# 3_ports.net
KiCad netlist of a schematic drawn in Altium Designer
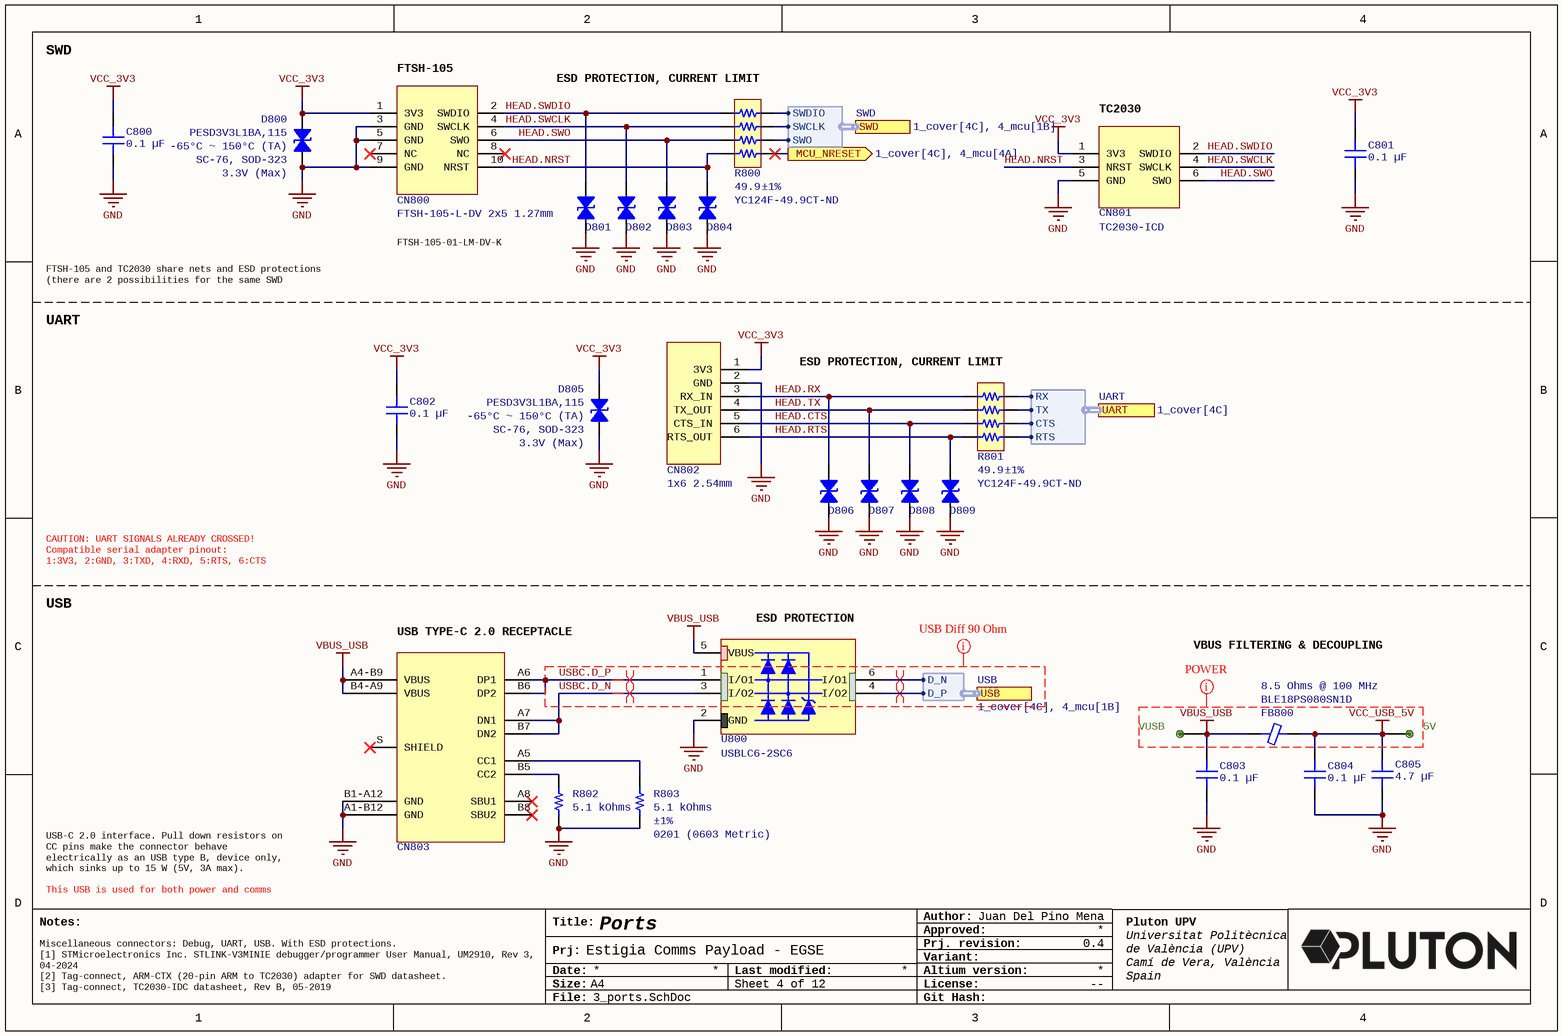
[diagram p0: 3_ports.SchDoc]

(export (version "E")
  (design (tool "Eeschema 10.0.6"))
  (components
    (comp (ref "5V")
      (value "~")
      (footprint "testpoints:testpoint_via")
      (description "Test point, thru-hole")
      (libsource (lib "testpoints") (part "TestPoint-VIA"))
    )
    (comp (ref "C800")
      (value "0.1 µF")
      (footprint "CAP 0402_1005")
      (description "CAP CER 0402 0.1UF 16V X7R 10%")
      (fields (field (name "PART NUMBER") "C0402C104K4RECAUTO") (field (name "MANUFACTURER") "KEMET"))
      (libsource (lib "Celestial Altium Library - altium_library") (part "Capacitor"))
    )
    (comp (ref "C801")
      (value "0.1 µF")
      (footprint "CAP 0402_1005")
      (description "CAP CER 0402 0.1UF 16V X7R 10%")
      (fields (field (name "PART NUMBER") "C0402C104K4RECAUTO") (field (name "MANUFACTURER") "KEMET"))
      (libsource (lib "Celestial Altium Library - altium_library") (part "Capacitor"))
    )
    (comp (ref "C802")
      (value "0.1 µF")
      (footprint "CAP 0402_1005")
      (description "CAP CER 0402 0.1UF 16V X7R 10%")
      (fields (field (name "PART NUMBER") "C0402C104K4RECAUTO") (field (name "MANUFACTURER") "KEMET"))
      (libsource (lib "Celestial Altium Library - altium_library") (part "Capacitor"))
    )
    (comp (ref "C803")
      (value "0.1 µF")
      (footprint "CAP 0402_1005")
      (description "CAP CER 0402 0.1UF 16V X7R 10%")
      (fields (field (name "PART NUMBER") "C0402C104K4RECAUTO") (field (name "MANUFACTURER") "KEMET"))
      (libsource (lib "Celestial Altium Library - altium_library") (part "Capacitor"))
    )
    (comp (ref "C804")
      (value "0.1 µF")
      (footprint "CAP 0402_1005")
      (description "CAP CER 0402 0.1UF 16V X7R 10%")
      (fields (field (name "PART NUMBER") "C0402C104K4RECAUTO") (field (name "MANUFACTURER") "KEMET"))
      (libsource (lib "Celestial Altium Library - altium_library") (part "Capacitor"))
    )
    (comp (ref "C805")
      (value "4.7 µF")
      (footprint "CAP 0603_1608")
      (description "CAP CER 4.7UF 16V X7R 0603")
      (fields
        (field (name "PART NUMBER") "GRM188Z71C475KE21J")
        (field (name "MANUFACTURER") "Murata Electronics")
      )
      (libsource (lib "Celestial Altium Library - altium_library") (part "Capacitor"))
    )
    (comp (ref "CN800")
      (value "FTSH-105-L-DV 2x5 1.27mm")
      (footprint "connectors:Samtec ftsh-105-l-dv")
      (description "Samtec FTSH-105-L-DV")
      (libsource (lib "connectors") (part "SWD Header 2x5 1.27mm"))
    )
    (comp (ref "CN801")
      (value "TC2030-ICD")
      (footprint "TC2030-MCP-NL")
      (libsource (lib "TC2030") (part "TC2030-ICD"))
    )
    (comp (ref "CN802")
      (value "1x6 2.54mm")
      (footprint "CONNECTORS:Header 1x6 2.54mm")
      (description "Header 1x6 2.54mm")
      (libsource (lib "connectors") (part "UART Header 1x6 2.54mm"))
    )
    (comp (ref "CN803")
      (value "USB4105-GF-A")
      (footprint "connectors:USB4105-GF-A")
      (description "z")
      (libsource (lib "usb") (part "USB-C USB4105-GF-A"))
    )
    (comp (ref "D800")
      (value "PESD3V3L1BA,115")
      (footprint "SOD323")
      (description "TVS DIODE 3.3VWM 26VC SOD323")
      (fields
        (field (name "PART NUMBER") "PESD3V3L1BA,115")
        (field (name "MANUFACTURER") "Nexperia USA Inc.")
        (field (name "OPERATING TEMPERATURE") "-65°C ~ 150°C (TA)")
        (field (name "PACKAGE / CASE") "SC-76, SOD-323")
        (field (name "VOLTAGE - REVERSE STANDOFF (TYP)") "3.3V (Max)")
      )
      (libsource (lib "Celestial Altium Library - altium_library") (part "Diode TVS"))
    )
    (comp (ref "D801")
      (value "PESD3V3L1BA,115")
      (footprint "SOD323")
      (description "TVS DIODE 3.3VWM 26VC SOD323")
      (fields (field (name "MANUFACTURER") "Nexperia USA Inc."))
      (libsource (lib "Celestial Altium Library - altium_library") (part "Diode TVS"))
    )
    (comp (ref "D802")
      (value "PESD3V3L1BA,115")
      (footprint "SOD323")
      (description "TVS DIODE 3.3VWM 26VC SOD323")
      (fields (field (name "MANUFACTURER") "Nexperia USA Inc."))
      (libsource (lib "Celestial Altium Library - altium_library") (part "Diode TVS"))
    )
    (comp (ref "D803")
      (value "PESD3V3L1BA,115")
      (footprint "SOD323")
      (description "TVS DIODE 3.3VWM 26VC SOD323")
      (fields (field (name "MANUFACTURER") "Nexperia USA Inc."))
      (libsource (lib "Celestial Altium Library - altium_library") (part "Diode TVS"))
    )
    (comp (ref "D804")
      (value "PESD3V3L1BA,115")
      (footprint "SOD323")
      (description "TVS DIODE 3.3VWM 26VC SOD323")
      (fields (field (name "MANUFACTURER") "Nexperia USA Inc."))
      (libsource (lib "Celestial Altium Library - altium_library") (part "Diode TVS"))
    )
    (comp (ref "D805")
      (value "PESD3V3L1BA,115")
      (footprint "SOD323")
      (description "TVS DIODE 3.3VWM 26VC SOD323")
      (fields
        (field (name "PART NUMBER") "PESD3V3L1BA,115")
        (field (name "MANUFACTURER") "Nexperia USA Inc.")
        (field (name "OPERATING TEMPERATURE") "-65°C ~ 150°C (TA)")
        (field (name "PACKAGE / CASE") "SC-76, SOD-323")
        (field (name "VOLTAGE - REVERSE STANDOFF (TYP)") "3.3V (Max)")
      )
      (libsource (lib "Celestial Altium Library - altium_library") (part "Diode TVS"))
    )
    (comp (ref "D806")
      (value "PESD3V3L1BA,115")
      (footprint "SOD323")
      (description "TVS DIODE 3.3VWM 26VC SOD323")
      (fields (field (name "MANUFACTURER") "Nexperia USA Inc."))
      (libsource (lib "Celestial Altium Library - altium_library") (part "Diode TVS"))
    )
    (comp (ref "D807")
      (value "PESD3V3L1BA,115")
      (footprint "SOD323")
      (description "TVS DIODE 3.3VWM 26VC SOD323")
      (fields (field (name "MANUFACTURER") "Nexperia USA Inc."))
      (libsource (lib "Celestial Altium Library - altium_library") (part "Diode TVS"))
    )
    (comp (ref "D808")
      (value "PESD3V3L1BA,115")
      (footprint "SOD323")
      (description "TVS DIODE 3.3VWM 26VC SOD323")
      (fields (field (name "MANUFACTURER") "Nexperia USA Inc."))
      (libsource (lib "Celestial Altium Library - altium_library") (part "Diode TVS"))
    )
    (comp (ref "D809")
      (value "PESD3V3L1BA,115")
      (footprint "SOD323")
      (description "TVS DIODE 3.3VWM 26VC SOD323")
      (fields (field (name "MANUFACTURER") "Nexperia USA Inc."))
      (libsource (lib "Celestial Altium Library - altium_library") (part "Diode TVS"))
    )
    (comp (ref "FB800")
      (value "8.5 Ohms @ 100 MHz")
      (footprint "FER 0603_1608")
      (description "FERRITE BEAD 8.5 OHM 0603 1LN")
      (fields
        (field (name "PART NUMBER") "BLE18PS080SN1D")
        (field (name "IMPEDANCE @ FREQUENCY") "8.5 Ohms @ 100 MHz")
        (field (name "MANUFACTURER") "Murata Electronics")
      )
      (libsource (lib "Celestial Altium Library - altium_library") (part "Ferrite Chip"))
    )
    (comp (ref "R800")
      (value "YC124-FR-0749R9L")
      (footprint "RESNET 0804-8 CONVEX")
      (description "RES ARRAY 4 RES 49.9 OHM 0804")
      (fields
        (field (name "MANUFACTURER") "Yageo")
        (field (name "RESISTANCE (OHMS)") "49.9")
        (field (name "SUPPLIER PART NUMBER 1") "YC124F-49.9CT-ND")
        (field (name "TOLERANCE") "±1%")
      )
      (libsource (lib "Celestial Altium Library - altium_library") (part "Resistor Array (4 circuit)"))
    )
    (comp (ref "R801")
      (value "YC124-FR-0749R9L")
      (footprint "RESNET 0804-8 CONVEX")
      (description "RES ARRAY 4 RES 49.9 OHM 0804")
      (fields
        (field (name "MANUFACTURER") "Yageo")
        (field (name "RESISTANCE (OHMS)") "49.9")
        (field (name "SUPPLIER PART NUMBER 1") "YC124F-49.9CT-ND")
        (field (name "TOLERANCE") "±1%")
      )
      (libsource (lib "Celestial Altium Library - altium_library") (part "Resistor Array (4 circuit)"))
    )
    (comp (ref "R802")
      (value "5.1 kOhms")
      (footprint "RES 0201_0603")
      (description "RES SMD 5.1K OHM 1% 1/20W 0201")
      (fields (field (name "PART NUMBER") "AC0201FR-075K1L") (field (name "MANUFACTURER") "Yageo"))
      (libsource (lib "Celestial Altium Library - altium_library") (part "Resistor"))
    )
    (comp (ref "R803")
      (value "5.1 kOhms")
      (footprint "RES 0201_0603")
      (description "RES SMD 5.1K OHM 1% 1/20W 0201")
      (fields
        (field (name "PART NUMBER") "AC0201FR-075K1L")
        (field (name "DEVICE PACKAGE") "0201 (0603 Metric)")
        (field (name "MANUFACTURER") "Yageo")
        (field (name "TOLERANCE") "±1%")
      )
      (libsource (lib "Celestial Altium Library - altium_library") (part "Resistor"))
    )
    (comp (ref "U800")
      (value "USBLC6-2SC6")
      (footprint "ics:SOT23-6L")
      (libsource (lib "usb") (part "USBLC6-2SC6"))
    )
    (comp (ref "VUSB")
      (value "~")
      (footprint "testpoints:testpoint_via")
      (description "Test point, thru-hole")
      (libsource (lib "testpoints") (part "TestPoint-VIA"))
    )
  )
  (nets
    (net (code "4") (name "/CTS") (class "Default")
      (node (ref "R801") (pin "6") (pinfunction "6_6") (pintype "passive"))
    )
    (net (code "5") (name "/D_N") (class "Default")
      (node (ref "U800") (pin "6") (pinfunction "I/O1_6") (pintype "passive"))
    )
    (net (code "6") (name "/D_P") (class "Default")
      (node (ref "U800") (pin "4") (pinfunction "I/O2_4") (pintype "passive"))
    )
    (net (code "7") (name "/HEAD.CTS") (class "Default")
      (node (ref "CN802") (pin "5") (pinfunction "CTS_IN_5") (pintype "passive"))
      (node (ref "D808") (pin "2") (pinfunction "2_2") (pintype "passive"))
      (node (ref "R801") (pin "3") (pinfunction "3_3") (pintype "passive"))
    )
    (net (code "8") (name "/HEAD.NRST") (class "Default")
      (node (ref "CN800") (pin "10") (pinfunction "NRST_10") (pintype "passive"))
      (node (ref "CN801") (pin "3") (pinfunction "NRST_3") (pintype "passive"))
      (node (ref "D804") (pin "2") (pinfunction "2_2") (pintype "passive"))
      (node (ref "R800") (pin "4") (pinfunction "4_4") (pintype "passive"))
    )
    (net (code "9") (name "/HEAD.RTS") (class "Default")
      (node (ref "CN802") (pin "6") (pinfunction "RTS_OUT_6") (pintype "passive"))
      (node (ref "D809") (pin "2") (pinfunction "2_2") (pintype "passive"))
      (node (ref "R801") (pin "4") (pinfunction "4_4") (pintype "passive"))
    )
    (net (code "10") (name "/HEAD.RX") (class "Default")
      (node (ref "CN802") (pin "3") (pinfunction "RX_IN_3") (pintype "passive"))
      (node (ref "D806") (pin "2") (pinfunction "2_2") (pintype "passive"))
      (node (ref "R801") (pin "1") (pinfunction "1_1") (pintype "passive"))
    )
    (net (code "11") (name "/HEAD.SWCLK") (class "Default")
      (node (ref "CN800") (pin "4") (pinfunction "SWCLK_4") (pintype "passive"))
      (node (ref "CN801") (pin "4") (pinfunction "SWCLK_4") (pintype "passive"))
      (node (ref "D802") (pin "2") (pinfunction "2_2") (pintype "passive"))
      (node (ref "R800") (pin "2") (pinfunction "2_2") (pintype "passive"))
    )
    (net (code "12") (name "/HEAD.SWDIO") (class "Default")
      (node (ref "CN800") (pin "2") (pinfunction "SWDIO_2") (pintype "passive"))
      (node (ref "CN801") (pin "2") (pinfunction "SWDIO_2") (pintype "passive"))
      (node (ref "D801") (pin "2") (pinfunction "2_2") (pintype "passive"))
      (node (ref "R800") (pin "1") (pinfunction "1_1") (pintype "passive"))
    )
    (net (code "13") (name "/HEAD.SWO") (class "Default")
      (node (ref "CN800") (pin "6") (pinfunction "SWO_6") (pintype "passive"))
      (node (ref "CN801") (pin "6") (pinfunction "SWO_6") (pintype "passive"))
      (node (ref "D803") (pin "2") (pinfunction "2_2") (pintype "passive"))
      (node (ref "R800") (pin "3") (pinfunction "3_3") (pintype "passive"))
    )
    (net (code "14") (name "/HEAD.TX") (class "Default")
      (node (ref "CN802") (pin "4") (pinfunction "TX_OUT_4") (pintype "passive"))
      (node (ref "D807") (pin "2") (pinfunction "2_2") (pintype "passive"))
      (node (ref "R801") (pin "2") (pinfunction "2_2") (pintype "passive"))
    )
    (net (code "15") (name "/MCU_NRESET") (class "Default")
      (node (ref "R800") (pin "5") (pinfunction "5_5") (pintype "passive+no_connect"))
    )
    (net (code "16") (name "/RTS") (class "Default")
      (node (ref "R801") (pin "5") (pinfunction "5_5") (pintype "passive"))
    )
    (net (code "17") (name "/RX") (class "Default")
      (node (ref "R801") (pin "8") (pinfunction "8_8") (pintype "passive"))
    )
    (net (code "18") (name "/SWCLK") (class "Default")
      (node (ref "R800") (pin "7") (pinfunction "7_7") (pintype "passive"))
    )
    (net (code "19") (name "/SWDIO") (class "Default")
      (node (ref "R800") (pin "8") (pinfunction "8_8") (pintype "passive"))
    )
    (net (code "20") (name "/SWO") (class "Default")
      (node (ref "R800") (pin "6") (pinfunction "6_6") (pintype "passive"))
    )
    (net (code "21") (name "/TX") (class "Default")
      (node (ref "R801") (pin "7") (pinfunction "7_7") (pintype "passive"))
    )
    (net (code "22") (name "/USBC.D_N") (class "Default")
      (node (ref "CN803") (pin "A7") (pinfunction "DN1_A7") (pintype "passive"))
      (node (ref "CN803") (pin "B7") (pinfunction "DN2_B7") (pintype "passive"))
      (node (ref "U800") (pin "3") (pinfunction "I/O2_3") (pintype "passive"))
    )
    (net (code "23") (name "/USBC.D_P") (class "Default")
      (node (ref "CN803") (pin "A6") (pinfunction "DP1_A6") (pintype "passive"))
      (node (ref "CN803") (pin "B6") (pinfunction "DP2_B6") (pintype "passive"))
      (node (ref "U800") (pin "1") (pinfunction "I/O1_1") (pintype "passive"))
    )
    (net (code "27") (name "GND") (class "Default")
      (node (ref "C800") (pin "1") (pinfunction "1_1") (pintype "passive"))
      (node (ref "C801") (pin "1") (pinfunction "1_1") (pintype "passive"))
      (node (ref "C802") (pin "1") (pinfunction "1_1") (pintype "passive"))
      (node (ref "C803") (pin "1") (pinfunction "1_1") (pintype "passive"))
      (node (ref "C804") (pin "1") (pinfunction "1_1") (pintype "passive"))
      (node (ref "C805") (pin "1") (pinfunction "1_1") (pintype "passive"))
      (node (ref "CN800") (pin "3") (pinfunction "GND_3") (pintype "passive"))
      (node (ref "CN800") (pin "5") (pinfunction "GND_5") (pintype "passive"))
      (node (ref "CN800") (pin "9") (pinfunction "GND_9") (pintype "passive"))
      (node (ref "CN801") (pin "5") (pinfunction "GND_5") (pintype "passive"))
      (node (ref "CN802") (pin "2") (pinfunction "GND_2") (pintype "power_in"))
      (node (ref "CN803") (pin "A1-B12") (pinfunction "GND_A1-B12") (pintype "power_in"))
      (node (ref "CN803") (pin "B1-A12") (pinfunction "GND_B1-A12") (pintype "power_in"))
      (node (ref "D800") (pin "1") (pinfunction "1_1") (pintype "passive"))
      (node (ref "D801") (pin "1") (pinfunction "1_1") (pintype "passive"))
      (node (ref "D802") (pin "1") (pinfunction "1_1") (pintype "passive"))
      (node (ref "D803") (pin "1") (pinfunction "1_1") (pintype "passive"))
      (node (ref "D804") (pin "1") (pinfunction "1_1") (pintype "passive"))
      (node (ref "D805") (pin "1") (pinfunction "1_1") (pintype "passive"))
      (node (ref "D806") (pin "1") (pinfunction "1_1") (pintype "passive"))
      (node (ref "D807") (pin "1") (pinfunction "1_1") (pintype "passive"))
      (node (ref "D808") (pin "1") (pinfunction "1_1") (pintype "passive"))
      (node (ref "D809") (pin "1") (pinfunction "1_1") (pintype "passive"))
      (node (ref "R802") (pin "1") (pinfunction "1_1") (pintype "passive"))
      (node (ref "R803") (pin "1") (pinfunction "1_1") (pintype "passive"))
      (node (ref "U800") (pin "2") (pinfunction "GND_2") (pintype "passive"))
    )
    (net (code "28") (name "Net-(CN803-CC1)") (class "Default")
      (node (ref "CN803") (pin "A5") (pinfunction "CC1_A5") (pintype "passive"))
      (node (ref "R803") (pin "2") (pinfunction "2_2") (pintype "passive"))
    )
    (net (code "29") (name "Net-(CN803-CC2)") (class "Default")
      (node (ref "CN803") (pin "B5") (pinfunction "CC2_B5") (pintype "passive"))
      (node (ref "R802") (pin "2") (pinfunction "2_2") (pintype "passive"))
    )
    (net (code "30") (name "VBUS_USB") (class "Default")
      (node (ref "C803") (pin "2") (pinfunction "2_2") (pintype "passive"))
      (node (ref "CN803") (pin "A4-B9") (pinfunction "VBUS_A4-B9") (pintype "power_in"))
      (node (ref "CN803") (pin "B4-A9") (pinfunction "VBUS_B4-A9") (pintype "power_in"))
      (node (ref "FB800") (pin "1") (pinfunction "1_1") (pintype "passive"))
      (node (ref "U800") (pin "5") (pinfunction "VBUS_5") (pintype "passive"))
      (node (ref "VUSB") (pin "0") (pinfunction "0_0") (pintype "passive"))
    )
    (net (code "31") (name "VCC_3V3") (class "Default")
      (node (ref "C800") (pin "2") (pinfunction "2_2") (pintype "passive"))
      (node (ref "C801") (pin "2") (pinfunction "2_2") (pintype "passive"))
      (node (ref "C802") (pin "2") (pinfunction "2_2") (pintype "passive"))
      (node (ref "CN800") (pin "1") (pinfunction "3V3_1") (pintype "passive"))
      (node (ref "CN801") (pin "1") (pinfunction "3V3_1") (pintype "passive"))
      (node (ref "CN802") (pin "1") (pinfunction "3V3_1") (pintype "power_in"))
      (node (ref "D800") (pin "2") (pinfunction "2_2") (pintype "passive"))
      (node (ref "D805") (pin "2") (pinfunction "2_2") (pintype "passive"))
    )
    (net (code "32") (name "VCC_USB_5V") (class "Default")
      (node (ref "5V") (pin "0") (pinfunction "0_0") (pintype "passive"))
      (node (ref "C804") (pin "2") (pinfunction "2_2") (pintype "passive"))
      (node (ref "C805") (pin "2") (pinfunction "2_2") (pintype "passive"))
      (node (ref "FB800") (pin "2") (pinfunction "2_2") (pintype "passive"))
    )
    (net (code "33") (name "unconnected-(CN800-NC-Pad7)") (class "Default")
      (node (ref "CN800") (pin "7") (pinfunction "NC_7") (pintype "passive+no_connect"))
    )
    (net (code "34") (name "unconnected-(CN800-NC-Pad8)") (class "Default")
      (node (ref "CN800") (pin "8") (pinfunction "NC_8") (pintype "passive+no_connect"))
    )
    (net (code "35") (name "unconnected-(CN803-SBU1-PadA8)") (class "Default")
      (node (ref "CN803") (pin "A8") (pinfunction "SBU1_A8") (pintype "passive+no_connect"))
    )
    (net (code "36") (name "unconnected-(CN803-SBU2-PadB8)") (class "Default")
      (node (ref "CN803") (pin "B8") (pinfunction "SBU2_B8") (pintype "passive+no_connect"))
    )
    (net (code "37") (name "unconnected-(CN803-SHIELD-PadS)") (class "Default")
      (node (ref "CN803") (pin "S") (pinfunction "SHIELD_S") (pintype "passive+no_connect"))
    )
  )
)
